# Sheet3.net
KiCad netlist of a schematic drawn in Altium Designer
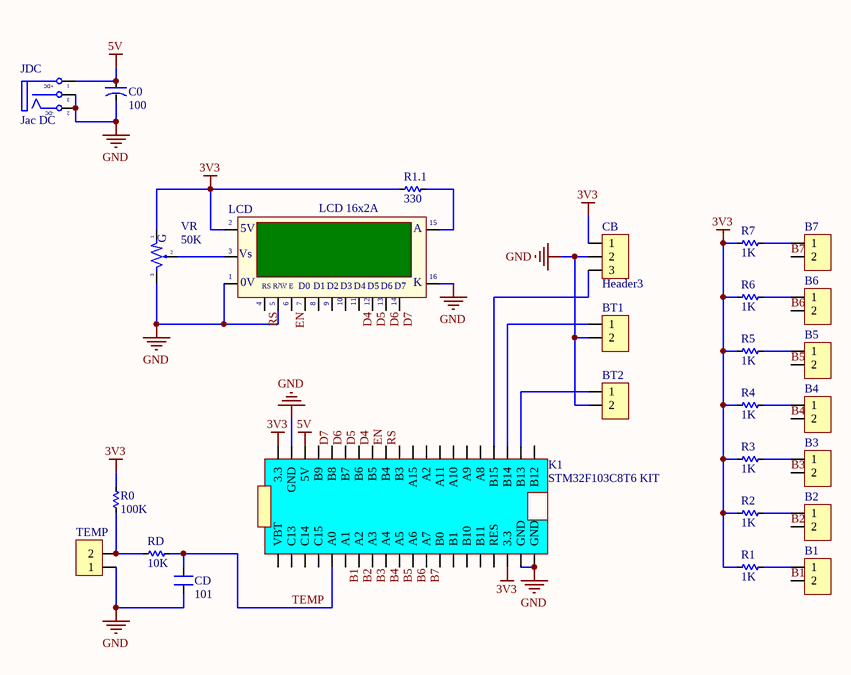
[diagram p0: Sheet3.SchDoc]

(export (version "E")
  (design (tool "Eeschema 10.0.6"))
  (components
    (comp (ref "B1")
      (value "~")
      (footprint "Header2")
      (description "Header IDC, 2 x 1 Pin Vertical 2.54mm Pitch (Non-Boxed, Male)")
      (fields
        (field (name "MANUFACTURER") "Würth Elektronik eiSos GmbH")
        (field (name "PARTNO") "613002143121")
        (field (name "CREATED BY") "Karrer Zheng")
      )
      (libsource (lib "LIBRARY") (part "Header2"))
    )
    (comp (ref "B2")
      (value "~")
      (footprint "Header2")
      (description "Header IDC, 2 x 1 Pin Vertical 2.54mm Pitch (Non-Boxed, Male)")
      (fields
        (field (name "MANUFACTURER") "Würth Elektronik eiSos GmbH")
        (field (name "PARTNO") "613002143121")
        (field (name "CREATED BY") "Karrer Zheng")
      )
      (libsource (lib "LIBRARY") (part "Header2"))
    )
    (comp (ref "B3")
      (value "~")
      (footprint "Header2")
      (description "Header IDC, 2 x 1 Pin Vertical 2.54mm Pitch (Non-Boxed, Male)")
      (fields
        (field (name "MANUFACTURER") "Würth Elektronik eiSos GmbH")
        (field (name "PARTNO") "613002143121")
        (field (name "CREATED BY") "Karrer Zheng")
      )
      (libsource (lib "LIBRARY") (part "Header2"))
    )
    (comp (ref "B4")
      (value "~")
      (footprint "Header2")
      (description "Header IDC, 2 x 1 Pin Vertical 2.54mm Pitch (Non-Boxed, Male)")
      (fields
        (field (name "MANUFACTURER") "Würth Elektronik eiSos GmbH")
        (field (name "PARTNO") "613002143121")
        (field (name "CREATED BY") "Karrer Zheng")
      )
      (libsource (lib "LIBRARY") (part "Header2"))
    )
    (comp (ref "B5")
      (value "~")
      (footprint "Header2")
      (description "Header IDC, 2 x 1 Pin Vertical 2.54mm Pitch (Non-Boxed, Male)")
      (fields
        (field (name "MANUFACTURER") "Würth Elektronik eiSos GmbH")
        (field (name "PARTNO") "613002143121")
        (field (name "CREATED BY") "Karrer Zheng")
      )
      (libsource (lib "LIBRARY") (part "Header2"))
    )
    (comp (ref "B6")
      (value "~")
      (footprint "Header2")
      (description "Header IDC, 2 x 1 Pin Vertical 2.54mm Pitch (Non-Boxed, Male)")
      (fields
        (field (name "MANUFACTURER") "Würth Elektronik eiSos GmbH")
        (field (name "PARTNO") "613002143121")
        (field (name "CREATED BY") "Karrer Zheng")
      )
      (libsource (lib "LIBRARY") (part "Header2"))
    )
    (comp (ref "B7")
      (value "~")
      (footprint "Header2")
      (description "Header IDC, 2 x 1 Pin Vertical 2.54mm Pitch (Non-Boxed, Male)")
      (fields
        (field (name "MANUFACTURER") "Würth Elektronik eiSos GmbH")
        (field (name "PARTNO") "613002143121")
        (field (name "CREATED BY") "Karrer Zheng")
      )
      (libsource (lib "LIBRARY") (part "Header2"))
    )
    (comp (ref "BT1")
      (value "~")
      (footprint "Header2")
      (description "Header IDC, 2 x 1 Pin Vertical 2.54mm Pitch (Non-Boxed, Male)")
      (fields
        (field (name "MANUFACTURER") "Würth Elektronik eiSos GmbH")
        (field (name "PARTNO") "613002143121")
        (field (name "CREATED BY") "Karrer Zheng")
      )
      (libsource (lib "LIBRARY") (part "Header2"))
    )
    (comp (ref "BT2")
      (value "~")
      (footprint "Header2")
      (description "Header IDC, 2 x 1 Pin Vertical 2.54mm Pitch (Non-Boxed, Male)")
      (fields
        (field (name "MANUFACTURER") "Würth Elektronik eiSos GmbH")
        (field (name "PARTNO") "613002143121")
        (field (name "CREATED BY") "Karrer Zheng")
      )
      (libsource (lib "LIBRARY") (part "Header2"))
    )
    (comp (ref "C0")
      (value "100")
      (footprint "CA-ALU-8")
      (description "Capacitor (Semiconductor SIM Model)")
      (fields (field (name "PUBLISHER") "Altium Limited"))
      (libsource (lib "LIBRARY") (part "CN-ALU-DIP"))
    )
    (comp (ref "CB")
      (value "Header3")
      (footprint "Header3")
      (description "Header IDC, 3 x 1 Pin Vertical 2.54mm Pitch (Non-Boxed, Male)")
      (fields
        (field (name "MANUFACTURER") "Würth Elektronik eiSos GmbH")
        (field (name "PARTNO") "613002143121")
        (field (name "CREATED BY") "Karrer Zheng")
      )
      (libsource (lib "LIBRARY") (part "Header3"))
    )
    (comp (ref "CD") (value "101") (footprint "CN1.5") (libsource (lib "LIBRARY") (part "CN")))
    (comp (ref "JDC")
      (value "Jac DC")
      (footprint "DC5")
      (description "Jac DC input")
      (libsource (lib "LIBRARY") (part "DCIN"))
    )
    (comp (ref "K1")
      (value "STM32F103C8T6 KIT")
      (footprint "STM32F103C8T6 KIT")
      (libsource (lib "TrongCz") (part "STM32F103C8T6 KIT"))
    )
    (comp (ref "LCD")
      (value "LCD 16x2A")
      (footprint "LCD16X2")
      (description "LCD dipslay 16 char, 2 line")
      (libsource (lib "LIBRARY") (part "LCD16x2A"))
    )
    (comp (ref "R0")
      (value "100K")
      (footprint "RES-1/4W")
      (description "Res")
      (fields
        (field (name "MANUFACTURER") "Generic Components")
        (field (name "PUBLISHER") "Altium Hobart Technology Centre")
      )
      (libsource (lib "LIBRARY") (part "Res"))
    )
    (comp (ref "R1")
      (value "1K")
      (footprint "RES-1/4W")
      (description "Res")
      (fields
        (field (name "MANUFACTURER") "Generic Components")
        (field (name "PUBLISHER") "Altium Hobart Technology Centre")
      )
      (libsource (lib "LIBRARY") (part "Res"))
    )
    (comp (ref "R1.1")
      (value "330")
      (footprint "RES-1/4W")
      (description "Res")
      (fields
        (field (name "MANUFACTURER") "Generic Components")
        (field (name "PUBLISHER") "Altium Hobart Technology Centre")
      )
      (libsource (lib "LIBRARY") (part "Res"))
    )
    (comp (ref "R2")
      (value "1K")
      (footprint "RES-1/4W")
      (description "Res")
      (fields
        (field (name "MANUFACTURER") "Generic Components")
        (field (name "PUBLISHER") "Altium Hobart Technology Centre")
      )
      (libsource (lib "LIBRARY") (part "Res"))
    )
    (comp (ref "R3")
      (value "1K")
      (footprint "RES-1/4W")
      (description "Res")
      (fields
        (field (name "MANUFACTURER") "Generic Components")
        (field (name "PUBLISHER") "Altium Hobart Technology Centre")
      )
      (libsource (lib "LIBRARY") (part "Res"))
    )
    (comp (ref "R4")
      (value "1K")
      (footprint "RES-1/4W")
      (description "Res")
      (fields
        (field (name "MANUFACTURER") "Generic Components")
        (field (name "PUBLISHER") "Altium Hobart Technology Centre")
      )
      (libsource (lib "LIBRARY") (part "Res"))
    )
    (comp (ref "R5")
      (value "1K")
      (footprint "RES-1/4W")
      (description "Res")
      (fields
        (field (name "MANUFACTURER") "Generic Components")
        (field (name "PUBLISHER") "Altium Hobart Technology Centre")
      )
      (libsource (lib "LIBRARY") (part "Res"))
    )
    (comp (ref "R6")
      (value "1K")
      (footprint "RES-1/4W")
      (description "Res")
      (fields
        (field (name "MANUFACTURER") "Generic Components")
        (field (name "PUBLISHER") "Altium Hobart Technology Centre")
      )
      (libsource (lib "LIBRARY") (part "Res"))
    )
    (comp (ref "R7")
      (value "1K")
      (footprint "RES-1/4W")
      (description "Res")
      (fields
        (field (name "MANUFACTURER") "Generic Components")
        (field (name "PUBLISHER") "Altium Hobart Technology Centre")
      )
      (libsource (lib "LIBRARY") (part "Res"))
    )
    (comp (ref "RD")
      (value "10K")
      (footprint "RES-1/4W")
      (description "Res")
      (fields
        (field (name "MANUFACTURER") "Generic Components")
        (field (name "PUBLISHER") "Altium Hobart Technology Centre")
      )
      (libsource (lib "LIBRARY") (part "Res"))
    )
    (comp (ref "TEMP")
      (value "~")
      (footprint "Header2")
      (description "Header IDC, 2 x 1 Pin Vertical 2.54mm Pitch (Non-Boxed, Male)")
      (fields
        (field (name "MANUFACTURER") "Würth Elektronik eiSos GmbH")
        (field (name "PARTNO") "613002143121")
        (field (name "CREATED BY") "Karrer Zheng")
      )
      (libsource (lib "") (part "Header2_1"))
    )
    (comp (ref "VR")
      (value "50K")
      (footprint "VR-S2")
      (description "Var Resistor")
      (libsource (lib "LIBRARY") (part "VR-S"))
    )
  )
  (nets
    (net (code "1") (name "/B1") (class "Default")
      (node (ref "B1") (pin "2") (pinfunction "2_2") (pintype "passive"))
      (node (ref "K1") (pin "6") (pinfunction "A1_6") (pintype "passive"))
    )
    (net (code "2") (name "/B2") (class "Default")
      (node (ref "B2") (pin "2") (pinfunction "2_2") (pintype "passive"))
      (node (ref "K1") (pin "7") (pinfunction "A2_7") (pintype "passive"))
    )
    (net (code "3") (name "/B3") (class "Default")
      (node (ref "B3") (pin "2") (pinfunction "2_2") (pintype "passive"))
      (node (ref "K1") (pin "8") (pinfunction "A3_8") (pintype "passive"))
    )
    (net (code "4") (name "/B4") (class "Default")
      (node (ref "B4") (pin "2") (pinfunction "2_2") (pintype "passive"))
      (node (ref "K1") (pin "9") (pinfunction "A4_9") (pintype "passive"))
    )
    (net (code "5") (name "/B5") (class "Default")
      (node (ref "B5") (pin "2") (pinfunction "2_2") (pintype "passive"))
      (node (ref "K1") (pin "10") (pinfunction "A5_10") (pintype "passive"))
    )
    (net (code "6") (name "/B6") (class "Default")
      (node (ref "B6") (pin "2") (pinfunction "2_2") (pintype "passive"))
      (node (ref "K1") (pin "11") (pinfunction "A6_11") (pintype "passive"))
    )
    (net (code "7") (name "/B7") (class "Default")
      (node (ref "B7") (pin "2") (pinfunction "2_2") (pintype "passive"))
      (node (ref "K1") (pin "12") (pinfunction "A7_12") (pintype "passive"))
    )
    (net (code "8") (name "/D4") (class "Default")
      (node (ref "K1") (pin "33") (pinfunction "B5_33") (pintype "passive"))
      (node (ref "LCD") (pin "11") (pinfunction "D4_11") (pintype "passive"))
    )
    (net (code "9") (name "/D5") (class "Default")
      (node (ref "K1") (pin "34") (pinfunction "B6_34") (pintype "passive"))
      (node (ref "LCD") (pin "12") (pinfunction "D5_12") (pintype "passive"))
    )
    (net (code "10") (name "/D6") (class "Default")
      (node (ref "K1") (pin "35") (pinfunction "B7_35") (pintype "passive"))
      (node (ref "LCD") (pin "13") (pinfunction "D6_13") (pintype "passive"))
    )
    (net (code "11") (name "/D7") (class "Default")
      (node (ref "K1") (pin "36") (pinfunction "B8_36") (pintype "passive"))
      (node (ref "LCD") (pin "14") (pinfunction "D7_14") (pintype "passive"))
    )
    (net (code "12") (name "/EN") (class "Default")
      (node (ref "K1") (pin "32") (pinfunction "B4_32") (pintype "passive"))
      (node (ref "LCD") (pin "6") (pinfunction "~{EN}_6") (pintype "passive"))
    )
    (net (code "13") (name "/RS") (class "Default")
      (node (ref "K1") (pin "31") (pinfunction "B3_31") (pintype "passive"))
      (node (ref "LCD") (pin "4") (pinfunction "RS_4") (pintype "passive"))
    )
    (net (code "14") (name "/TEMP") (class "Default")
      (node (ref "CD") (pin "2") (pinfunction "2_2") (pintype "passive"))
      (node (ref "K1") (pin "5") (pinfunction "A0_5") (pintype "passive"))
      (node (ref "RD") (pin "2") (pinfunction "2_2") (pintype "passive"))
    )
    (net (code "15") (name "3V3") (class "Default")
      (node (ref "CB") (pin "1") (pinfunction "1_1") (pintype "passive"))
      (node (ref "K1") (pin "18") (pinfunction "3.3_18") (pintype "passive"))
      (node (ref "K1") (pin "40") (pinfunction "3.3_40") (pintype "passive"))
      (node (ref "LCD") (pin "2") (pinfunction "VDD_2") (pintype "passive"))
      (node (ref "R0") (pin "1") (pinfunction "1_1") (pintype "passive"))
      (node (ref "R1") (pin "2") (pinfunction "2_2") (pintype "passive"))
      (node (ref "R1.1") (pin "2") (pinfunction "2_2") (pintype "passive"))
      (node (ref "R2") (pin "2") (pinfunction "2_2") (pintype "passive"))
      (node (ref "R3") (pin "2") (pinfunction "2_2") (pintype "passive"))
      (node (ref "R4") (pin "2") (pinfunction "2_2") (pintype "passive"))
      (node (ref "R5") (pin "2") (pinfunction "2_2") (pintype "passive"))
      (node (ref "R6") (pin "2") (pinfunction "2_2") (pintype "passive"))
      (node (ref "R7") (pin "2") (pinfunction "2_2") (pintype "passive"))
      (node (ref "VR") (pin "1") (pinfunction "1_1") (pintype "passive"))
    )
    (net (code "16") (name "5V") (class "Default")
      (node (ref "C0") (pin "1") (pinfunction "1_1") (pintype "passive"))
      (node (ref "JDC") (pin "1") (pinfunction "T_1") (pintype "passive"))
      (node (ref "K1") (pin "38") (pinfunction "5V_38") (pintype "passive"))
    )
    (net (code "17") (name "GND") (class "Default")
      (node (ref "BT1") (pin "2") (pinfunction "2_2") (pintype "passive"))
      (node (ref "BT2") (pin "2") (pinfunction "2_2") (pintype "passive"))
      (node (ref "C0") (pin "2") (pinfunction "2_2") (pintype "passive"))
      (node (ref "CB") (pin "2") (pinfunction "2_2") (pintype "passive"))
      (node (ref "CD") (pin "1") (pinfunction "1_1") (pintype "passive"))
      (node (ref "JDC") (pin "2") (pinfunction "TN_2") (pintype "passive"))
      (node (ref "JDC") (pin "3") (pinfunction "S_3") (pintype "power_in"))
      (node (ref "K1") (pin "19") (pinfunction "GND_19") (pintype "passive"))
      (node (ref "K1") (pin "20") (pinfunction "GND_20") (pintype "passive"))
      (node (ref "K1") (pin "39") (pinfunction "GND_39") (pintype "passive"))
      (node (ref "LCD") (pin "1") (pinfunction "GND_1") (pintype "passive"))
      (node (ref "LCD") (pin "16") (pinfunction "K_16") (pintype "passive"))
      (node (ref "LCD") (pin "5") (pinfunction "R/~{W}_5") (pintype "passive"))
      (node (ref "TEMP") (pin "1") (pinfunction "1_1") (pintype "passive"))
      (node (ref "VR") (pin "3") (pinfunction "3_3") (pintype "passive"))
    )
    (net (code "18") (name "Net-(B1-Pad1)") (class "Default")
      (node (ref "B1") (pin "1") (pinfunction "1_1") (pintype "passive"))
      (node (ref "R1") (pin "1") (pinfunction "1_1") (pintype "passive"))
    )
    (net (code "19") (name "Net-(B2-Pad1)") (class "Default")
      (node (ref "B2") (pin "1") (pinfunction "1_1") (pintype "passive"))
      (node (ref "R2") (pin "1") (pinfunction "1_1") (pintype "passive"))
    )
    (net (code "20") (name "Net-(B3-Pad1)") (class "Default")
      (node (ref "B3") (pin "1") (pinfunction "1_1") (pintype "passive"))
      (node (ref "R3") (pin "1") (pinfunction "1_1") (pintype "passive"))
    )
    (net (code "21") (name "Net-(B4-Pad1)") (class "Default")
      (node (ref "B4") (pin "1") (pinfunction "1_1") (pintype "passive"))
      (node (ref "R4") (pin "1") (pinfunction "1_1") (pintype "passive"))
    )
    (net (code "22") (name "Net-(B5-Pad1)") (class "Default")
      (node (ref "B5") (pin "1") (pinfunction "1_1") (pintype "passive"))
      (node (ref "R5") (pin "1") (pinfunction "1_1") (pintype "passive"))
    )
    (net (code "23") (name "Net-(B6-Pad1)") (class "Default")
      (node (ref "B6") (pin "1") (pinfunction "1_1") (pintype "passive"))
      (node (ref "R6") (pin "1") (pinfunction "1_1") (pintype "passive"))
    )
    (net (code "24") (name "Net-(B7-Pad1)") (class "Default")
      (node (ref "B7") (pin "1") (pinfunction "1_1") (pintype "passive"))
      (node (ref "R7") (pin "1") (pinfunction "1_1") (pintype "passive"))
    )
    (net (code "25") (name "Net-(K1-B13)") (class "Default")
      (node (ref "BT2") (pin "1") (pinfunction "1_1") (pintype "passive"))
      (node (ref "K1") (pin "22") (pinfunction "B13_22") (pintype "passive"))
    )
    (net (code "26") (name "Net-(K1-B14)") (class "Default")
      (node (ref "BT1") (pin "1") (pinfunction "1_1") (pintype "passive"))
      (node (ref "K1") (pin "23") (pinfunction "B14_23") (pintype "passive"))
    )
    (net (code "27") (name "Net-(K1-B15)") (class "Default")
      (node (ref "CB") (pin "3") (pinfunction "3_3") (pintype "passive"))
      (node (ref "K1") (pin "24") (pinfunction "B15_24") (pintype "passive"))
    )
    (net (code "28") (name "Net-(LCD-A)") (class "Default")
      (node (ref "LCD") (pin "15") (pinfunction "A_15") (pintype "passive"))
      (node (ref "R1.1") (pin "1") (pinfunction "1_1") (pintype "passive"))
    )
    (net (code "29") (name "Net-(LCD-VEE)") (class "Default")
      (node (ref "LCD") (pin "3") (pinfunction "VEE_3") (pintype "passive"))
      (node (ref "VR") (pin "2") (pinfunction "2_2") (pintype "passive"))
    )
    (net (code "30") (name "Net-(R0-Pad2)") (class "Default")
      (node (ref "R0") (pin "2") (pinfunction "2_2") (pintype "passive"))
      (node (ref "RD") (pin "1") (pinfunction "1_1") (pintype "passive"))
      (node (ref "TEMP") (pin "2") (pinfunction "2_2") (pintype "passive"))
    )
    (net (code "31") (name "unconnected-(K1-A2-Pad29)") (class "Default")
      (node (ref "K1") (pin "29") (pinfunction "A2_29") (pintype "passive"))
    )
    (net (code "32") (name "unconnected-(K1-A8-Pad25)") (class "Default")
      (node (ref "K1") (pin "25") (pinfunction "A8_25") (pintype "passive"))
    )
    (net (code "33") (name "unconnected-(K1-A9-Pad26)") (class "Default")
      (node (ref "K1") (pin "26") (pinfunction "A9_26") (pintype "passive"))
    )
    (net (code "34") (name "unconnected-(K1-A10-Pad27)") (class "Default")
      (node (ref "K1") (pin "27") (pinfunction "A10_27") (pintype "passive"))
    )
    (net (code "35") (name "unconnected-(K1-A11-Pad28)") (class "Default")
      (node (ref "K1") (pin "28") (pinfunction "A11_28") (pintype "passive"))
    )
    (net (code "36") (name "unconnected-(K1-A15-Pad30)") (class "Default")
      (node (ref "K1") (pin "30") (pinfunction "A15_30") (pintype "passive"))
    )
    (net (code "37") (name "unconnected-(K1-B0-Pad13)") (class "Default")
      (node (ref "K1") (pin "13") (pinfunction "B0_13") (pintype "passive"))
    )
    (net (code "38") (name "unconnected-(K1-B1-Pad14)") (class "Default")
      (node (ref "K1") (pin "14") (pinfunction "B1_14") (pintype "passive"))
    )
    (net (code "39") (name "unconnected-(K1-B9-Pad37)") (class "Default")
      (node (ref "K1") (pin "37") (pinfunction "B9_37") (pintype "passive"))
    )
    (net (code "40") (name "unconnected-(K1-B10-Pad15)") (class "Default")
      (node (ref "K1") (pin "15") (pinfunction "B10_15") (pintype "passive"))
    )
    (net (code "41") (name "unconnected-(K1-B11-Pad16)") (class "Default")
      (node (ref "K1") (pin "16") (pinfunction "B11_16") (pintype "passive"))
    )
    (net (code "42") (name "unconnected-(K1-B12-Pad21)") (class "Default")
      (node (ref "K1") (pin "21") (pinfunction "B12_21") (pintype "passive"))
    )
    (net (code "43") (name "unconnected-(K1-C13-Pad2)") (class "Default")
      (node (ref "K1") (pin "2") (pinfunction "C13_2") (pintype "passive"))
    )
    (net (code "44") (name "unconnected-(K1-C14-Pad3)") (class "Default")
      (node (ref "K1") (pin "3") (pinfunction "C14_3") (pintype "passive"))
    )
    (net (code "45") (name "unconnected-(K1-C15-Pad4)") (class "Default")
      (node (ref "K1") (pin "4") (pinfunction "C15_4") (pintype "passive"))
    )
    (net (code "46") (name "unconnected-(K1-RES-Pad17)") (class "Default")
      (node (ref "K1") (pin "17") (pinfunction "RES_17") (pintype "passive"))
    )
    (net (code "47") (name "unconnected-(K1-VBT-Pad1)") (class "Default")
      (node (ref "K1") (pin "1") (pinfunction "VBT_1") (pintype "passive"))
    )
    (net (code "48") (name "unconnected-(LCD-D0-Pad7)") (class "Default")
      (node (ref "LCD") (pin "7") (pinfunction "D0_7") (pintype "passive"))
    )
    (net (code "49") (name "unconnected-(LCD-D1-Pad8)") (class "Default")
      (node (ref "LCD") (pin "8") (pinfunction "D1_8") (pintype "passive"))
    )
    (net (code "50") (name "unconnected-(LCD-D2-Pad9)") (class "Default")
      (node (ref "LCD") (pin "9") (pinfunction "D2_9") (pintype "passive"))
    )
    (net (code "51") (name "unconnected-(LCD-D3-Pad10)") (class "Default")
      (node (ref "LCD") (pin "10") (pinfunction "D3_10") (pintype "passive"))
    )
  )
)
